# AlienWhoopF7-ESP32.net
KiCad netlist of a schematic drawn in EAGLE
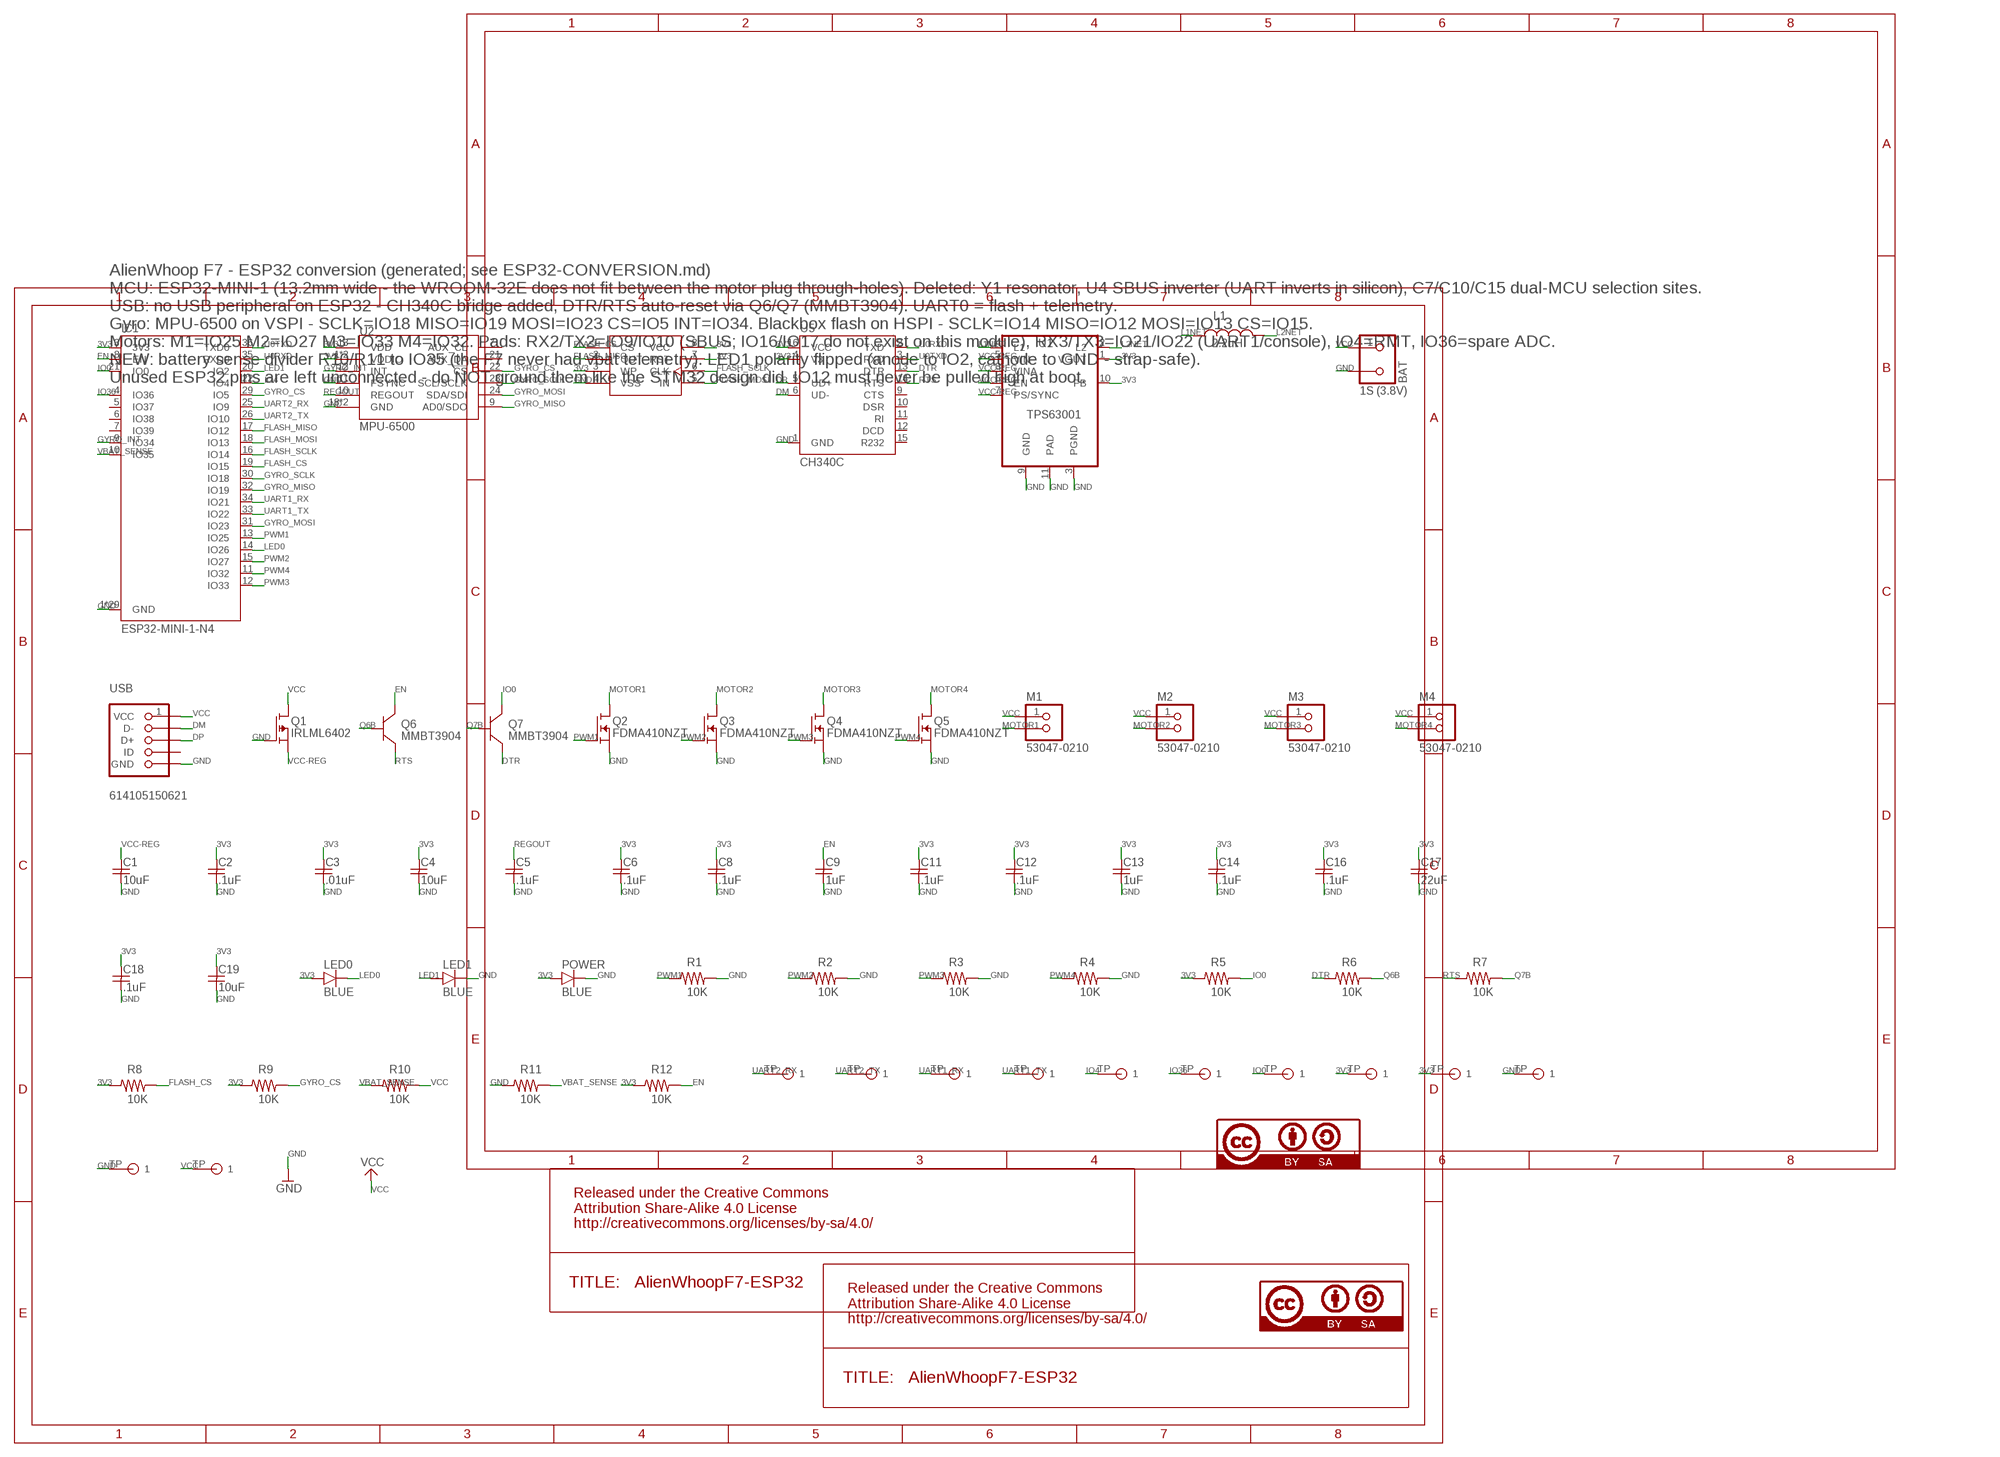
[diagram p0: schematic, sheet 1]

(export (version "E")
  (design (tool "Eeschema 10.0.6"))
  (components
    (comp (ref "3.3V")
      (value "TESTPAD")
      (footprint "eagle-import:TESTPAD")
      (libsource (lib "eagle-import") (part "TESTPAD"))
    )
    (comp (ref "3V3")
      (value "TESTPAD")
      (footprint "eagle-import:TESTPAD")
      (libsource (lib "eagle-import") (part "TESTPAD"))
    )
    (comp (ref "BAT")
      (value "1S (3.8V)")
      (footprint "eagle-import:S2B-PH-K-S")
      (fields (field (name "MF") "JST") (field (name "MPN") "S2B-PH-K-S"))
      (libsource (lib "eagle-import") (part "JST-PH-BAT"))
    )
    (comp (ref "BOOT")
      (value "TESTPAD")
      (footprint "eagle-import:TESTPAD")
      (libsource (lib "eagle-import") (part "TESTPAD"))
    )
    (comp (ref "C1")
      (value "10uF")
      (footprint "eagle-import:YUDEN-CAP-0805")
      (fields (field (name "MF") "Taiyo Yuden") (field (name "MPN") "JMK212AB7106KG-T"))
      (libsource (lib "eagle-import") (part "CAPACITOR10UF"))
    )
    (comp (ref "C2")
      (value ".1uF")
      (footprint "eagle-import:MUR-CAP-0603")
      (fields (field (name "MF") "Murata") (field (name "MPN") "GRM188R71C104KA01D"))
      (libsource (lib "eagle-import") (part "CAPACITOR.1UF"))
    )
    (comp (ref "C3")
      (value ".01uF")
      (footprint "eagle-import:MUR-CAP-0603")
      (fields (field (name "MF") "Murata") (field (name "MPN") "GRM188R71C103KA01D"))
      (libsource (lib "eagle-import") (part "CAPACITOR.01UF"))
    )
    (comp (ref "C4")
      (value "10uF")
      (footprint "eagle-import:YUDEN-CAP-0805")
      (fields (field (name "MF") "Taiyo Yuden") (field (name "MPN") "JMK212AB7106KG-T"))
      (libsource (lib "eagle-import") (part "CAPACITOR10UF"))
    )
    (comp (ref "C5")
      (value ".1uF")
      (footprint "eagle-import:MUR-CAP-0603")
      (fields (field (name "MF") "Murata") (field (name "MPN") "GRM188R71C104KA01D"))
      (libsource (lib "eagle-import") (part "CAPACITOR.1UF"))
    )
    (comp (ref "C6")
      (value ".1uF")
      (footprint "eagle-import:MUR-CAP-0603")
      (fields (field (name "MF") "Murata") (field (name "MPN") "GRM188R71C104KA01D"))
      (libsource (lib "eagle-import") (part "CAPACITOR.1UF"))
    )
    (comp (ref "C8")
      (value ".1uF")
      (footprint "eagle-import:MUR-CAP-0603")
      (fields (field (name "MF") "Murata") (field (name "MPN") "GRM188R71C104KA01D"))
      (libsource (lib "eagle-import") (part "CAPACITOR.1UF"))
    )
    (comp (ref "C9")
      (value "1uF")
      (footprint "eagle-import:MUR-CAP-0603")
      (fields (field (name "MF") "Murata") (field (name "MPN") "GRM188R71C105KA12D"))
      (libsource (lib "eagle-import") (part "CAPACITOR1UF"))
    )
    (comp (ref "C11")
      (value ".1uF")
      (footprint "eagle-import:MUR-CAP-0603")
      (fields (field (name "MF") "Murata") (field (name "MPN") "GRM188R71C104KA01D"))
      (libsource (lib "eagle-import") (part "CAPACITOR.1UF"))
    )
    (comp (ref "C12")
      (value ".1uF")
      (footprint "eagle-import:MUR-CAP-0603")
      (fields (field (name "MF") "Murata") (field (name "MPN") "GRM188R71C104KA01D"))
      (libsource (lib "eagle-import") (part "CAPACITOR.1UF"))
    )
    (comp (ref "C13")
      (value "1uF")
      (footprint "eagle-import:MUR-CAP-0603")
      (fields (field (name "MF") "Murata") (field (name "MPN") "GRM188R71C105KA12D"))
      (libsource (lib "eagle-import") (part "CAPACITOR1UF"))
    )
    (comp (ref "C14")
      (value ".1uF")
      (footprint "eagle-import:MUR-CAP-0603")
      (fields (field (name "MF") "Murata") (field (name "MPN") "GRM188R71C104KA01D"))
      (libsource (lib "eagle-import") (part "CAPACITOR.1UF"))
    )
    (comp (ref "C16")
      (value ".1uF")
      (footprint "eagle-import:MUR-CAP-0603")
      (fields (field (name "MF") "Murata") (field (name "MPN") "GRM188R71C104KA01D"))
      (libsource (lib "eagle-import") (part "CAPACITOR.1UF"))
    )
    (comp (ref "C17")
      (value "22uF")
      (footprint "eagle-import:YUDEN-CAP-0805")
      (fields (field (name "MF") "Taiyo Yuden") (field (name "MPN") "JMK212BJ226MG-T"))
      (libsource (lib "eagle-import") (part "CAPACITOR22UF"))
    )
    (comp (ref "C18")
      (value ".1uF")
      (footprint "eagle-import:MUR-CAP-0603")
      (fields (field (name "MF") "Murata") (field (name "MPN") "GRM188R71C104KA01D"))
      (libsource (lib "eagle-import") (part "CAPACITOR.1UF"))
    )
    (comp (ref "C19")
      (value "10uF")
      (footprint "eagle-import:YUDEN-CAP-0805")
      (fields (field (name "MF") "Taiyo Yuden") (field (name "MPN") "JMK212AB7106KG-T"))
      (libsource (lib "eagle-import") (part "CAPACITOR10UF"))
    )
    (comp (ref "GND")
      (value "TESTPAD")
      (footprint "eagle-import:TESTPAD")
      (libsource (lib "eagle-import") (part "TESTPAD"))
    )
    (comp (ref "GND@1")
      (value "TESTPAD")
      (footprint "eagle-import:TESTPAD")
      (libsource (lib "eagle-import") (part "TESTPAD"))
    )
    (comp (ref "IC1")
      (value "ESP32-MINI-1-N4")
      (footprint "eagle-import:ESP32-MINI-1")
      (libsource (lib "eagle-import") (part "ESP32-MINI-1"))
    )
    (comp (ref "IO4")
      (value "TESTPAD")
      (footprint "eagle-import:TESTPAD")
      (libsource (lib "eagle-import") (part "TESTPAD"))
    )
    (comp (ref "IO36")
      (value "TESTPAD")
      (footprint "eagle-import:TESTPAD")
      (libsource (lib "eagle-import") (part "TESTPAD"))
    )
    (comp (ref "L1")
      (value "2.2uH")
      (footprint "eagle-import:DFE201612E-2R2M-P2")
      (libsource (lib "eagle-import") (part "DFE201612E-2R2M-P2"))
    )
    (comp (ref "LED0")
      (value "BLUE")
      (footprint "eagle-import:SMD-CHIP-LED-0805")
      (fields (field (name "MF") "Kingbright") (field (name "MPN") "APHCM2012QBC/D-F01"))
      (libsource (lib "eagle-import") (part "SMD-CHIP-LED-0805"))
    )
    (comp (ref "LED1")
      (value "BLUE")
      (footprint "eagle-import:SMD-CHIP-LED-0805")
      (fields (field (name "MF") "Kingbright") (field (name "MPN") "APHCM2012QBC/D-F01"))
      (libsource (lib "eagle-import") (part "SMD-CHIP-LED-0805"))
    )
    (comp (ref "M1")
      (value "53047-0210")
      (footprint "eagle-import:PICO-53047-02")
      (fields (field (name "MF") "MOLEX"))
      (libsource (lib "eagle-import") (part "PICO-1.25-MOTOR"))
    )
    (comp (ref "M2")
      (value "53047-0210")
      (footprint "eagle-import:PICO-53047-02")
      (fields (field (name "MF") "MOLEX"))
      (libsource (lib "eagle-import") (part "PICO-1.25-MOTOR"))
    )
    (comp (ref "M3")
      (value "53047-0210")
      (footprint "eagle-import:PICO-53047-02")
      (fields (field (name "MF") "MOLEX"))
      (libsource (lib "eagle-import") (part "PICO-1.25-MOTOR"))
    )
    (comp (ref "M4")
      (value "53047-0210")
      (footprint "eagle-import:PICO-53047-02")
      (fields (field (name "MF") "MOLEX"))
      (libsource (lib "eagle-import") (part "PICO-1.25-MOTOR"))
    )
    (comp (ref "POWER")
      (value "BLUE")
      (footprint "eagle-import:SMD-CHIP-LED-0805")
      (fields (field (name "MF") "Kingbright") (field (name "MPN") "APHCM2012QBC/D-F01"))
      (libsource (lib "eagle-import") (part "SMD-CHIP-LED-0805"))
    )
    (comp (ref "Q1")
      (value "IRLML6402")
      (footprint "eagle-import:SOT-23")
      (fields (field (name "MF") "IR"))
      (libsource (lib "eagle-import") (part "MOSFET-P"))
    )
    (comp (ref "Q2")
      (value "FDMA410NZT")
      (footprint "eagle-import:MICROFET-2X2")
      (fields (field (name "MF") "Fairchild") (field (name "MPN") "FDMA410NZ"))
      (libsource (lib "eagle-import") (part "FDMA410NZ"))
    )
    (comp (ref "Q3")
      (value "FDMA410NZT")
      (footprint "eagle-import:MICROFET-2X2")
      (fields (field (name "MF") "Fairchild") (field (name "MPN") "FDMA410NZ"))
      (libsource (lib "eagle-import") (part "FDMA410NZ"))
    )
    (comp (ref "Q4")
      (value "FDMA410NZT")
      (footprint "eagle-import:MICROFET-2X2")
      (fields (field (name "MF") "Fairchild") (field (name "MPN") "FDMA410NZ"))
      (libsource (lib "eagle-import") (part "FDMA410NZ"))
    )
    (comp (ref "Q5")
      (value "FDMA410NZT")
      (footprint "eagle-import:MICROFET-2X2")
      (fields (field (name "MF") "Fairchild") (field (name "MPN") "FDMA410NZ"))
      (libsource (lib "eagle-import") (part "FDMA410NZ"))
    )
    (comp (ref "Q6")
      (value "MMBT3904")
      (footprint "eagle-import:SOT23")
      (libsource (lib "eagle-import") (part "MMBT3904"))
    )
    (comp (ref "Q7")
      (value "MMBT3904")
      (footprint "eagle-import:SOT23")
      (libsource (lib "eagle-import") (part "MMBT3904"))
    )
    (comp (ref "R1")
      (value "10K")
      (footprint "eagle-import:VISH-RES-0603")
      (fields (field (name "MF") "Vishay") (field (name "MPN") "CRCW060310K0FKEAHP"))
      (libsource (lib "eagle-import") (part "RESISTOR10K"))
    )
    (comp (ref "R2")
      (value "10K")
      (footprint "eagle-import:VISH-RES-0603")
      (fields (field (name "MF") "Vishay") (field (name "MPN") "CRCW060310K0FKEAHP"))
      (libsource (lib "eagle-import") (part "RESISTOR10K"))
    )
    (comp (ref "R3")
      (value "10K")
      (footprint "eagle-import:VISH-RES-0603")
      (fields (field (name "MF") "Vishay") (field (name "MPN") "CRCW060310K0FKEAHP"))
      (libsource (lib "eagle-import") (part "RESISTOR10K"))
    )
    (comp (ref "R4")
      (value "10K")
      (footprint "eagle-import:VISH-RES-0603")
      (fields (field (name "MF") "Vishay") (field (name "MPN") "CRCW060310K0FKEAHP"))
      (libsource (lib "eagle-import") (part "RESISTOR10K"))
    )
    (comp (ref "R5")
      (value "10K")
      (footprint "eagle-import:VISH-RES-0603")
      (fields (field (name "MF") "Vishay") (field (name "MPN") "CRCW060310K0FKEAHP"))
      (libsource (lib "eagle-import") (part "RESISTOR10K"))
    )
    (comp (ref "R6")
      (value "10K")
      (footprint "eagle-import:VISH-RES-0603")
      (fields (field (name "MF") "Vishay") (field (name "MPN") "CRCW060310K0FKEAHP"))
      (libsource (lib "eagle-import") (part "RESISTOR10K"))
    )
    (comp (ref "R7")
      (value "10K")
      (footprint "eagle-import:VISH-RES-0603")
      (fields (field (name "MF") "Vishay") (field (name "MPN") "CRCW060310K0FKEAHP"))
      (libsource (lib "eagle-import") (part "RESISTOR10K"))
    )
    (comp (ref "R8")
      (value "10K")
      (footprint "eagle-import:VISH-RES-0603")
      (fields (field (name "MF") "Vishay") (field (name "MPN") "CRCW060310K0FKEAHP"))
      (libsource (lib "eagle-import") (part "RESISTOR10K"))
    )
    (comp (ref "R9")
      (value "10K")
      (footprint "eagle-import:VISH-RES-0603")
      (fields (field (name "MF") "Vishay") (field (name "MPN") "CRCW060310K0FKEAHP"))
      (libsource (lib "eagle-import") (part "RESISTOR10K"))
    )
    (comp (ref "R10")
      (value "10K")
      (footprint "eagle-import:VISH-RES-0603")
      (fields (field (name "MF") "Vishay") (field (name "MPN") "CRCW060310K0FKEAHP"))
      (libsource (lib "eagle-import") (part "RESISTOR10K"))
    )
    (comp (ref "R11")
      (value "10K")
      (footprint "eagle-import:VISH-RES-0603")
      (fields (field (name "MF") "Vishay") (field (name "MPN") "CRCW060310K0FKEAHP"))
      (libsource (lib "eagle-import") (part "RESISTOR10K"))
    )
    (comp (ref "R12")
      (value "10K")
      (footprint "eagle-import:VISH-RES-0603")
      (fields (field (name "MF") "Vishay") (field (name "MPN") "CRCW060310K0FKEAHP"))
      (libsource (lib "eagle-import") (part "RESISTOR10K"))
    )
    (comp (ref "RX2")
      (value "TESTPAD")
      (footprint "eagle-import:TESTPAD")
      (libsource (lib "eagle-import") (part "TESTPAD"))
    )
    (comp (ref "RX3")
      (value "TESTPAD")
      (footprint "eagle-import:TESTPAD")
      (libsource (lib "eagle-import") (part "TESTPAD"))
    )
    (comp (ref "TX2")
      (value "TESTPAD")
      (footprint "eagle-import:TESTPAD")
      (libsource (lib "eagle-import") (part "TESTPAD"))
    )
    (comp (ref "TX3")
      (value "TESTPAD")
      (footprint "eagle-import:TESTPAD")
      (libsource (lib "eagle-import") (part "TESTPAD"))
    )
    (comp (ref "U1")
      (value "TPS63001")
      (footprint "eagle-import:VSON-N10")
      (fields (field (name "MF") "TI") (field (name "MPN") "TPS63001DRCR"))
      (libsource (lib "eagle-import") (part "TPS630XX-TPS63001"))
    )
    (comp (ref "U2")
      (value "MPU-6500")
      (footprint "eagle-import:QFN24_PAD")
      (libsource (lib "eagle-import") (part "MPU-9250"))
    )
    (comp (ref "U3")
      (value "MX25L6406EM2I-12G")
      (footprint "eagle-import:M25P32")
      (libsource (lib "eagle-import") (part "M25P32"))
    )
    (comp (ref "U5")
      (value "CH340C")
      (footprint "eagle-import:SOP16")
      (libsource (lib "eagle-import") (part "CH340C"))
    )
    (comp (ref "USB")
      (value "614105150621")
      (footprint "eagle-import:USB-BFPV")
      (libsource (lib "eagle-import") (part "MICROUSBUSB-BFPV"))
    )
    (comp (ref "VCC@1")
      (value "TESTPAD")
      (footprint "eagle-import:TESTPAD")
      (libsource (lib "eagle-import") (part "TESTPAD"))
    )
  )
  (nets
    (net (code "1") (name "/3V3") (class "Default")
      (node (ref "3.3V") (pin "TP") (pinfunction "1_TP") (pintype "bidirectional"))
      (node (ref "3V3") (pin "TP") (pinfunction "1_TP") (pintype "bidirectional"))
      (node (ref "C11") (pin "1") (pinfunction "1_1") (pintype "passive"))
      (node (ref "C12") (pin "1") (pinfunction "1_1") (pintype "passive"))
      (node (ref "C13") (pin "1") (pinfunction "1_1") (pintype "passive"))
      (node (ref "C14") (pin "1") (pinfunction "1_1") (pintype "passive"))
      (node (ref "C16") (pin "1") (pinfunction "1_1") (pintype "passive"))
      (node (ref "C17") (pin "1") (pinfunction "1_1") (pintype "passive"))
      (node (ref "C18") (pin "1") (pinfunction "1_1") (pintype "passive"))
      (node (ref "C19") (pin "1") (pinfunction "1_1") (pintype "passive"))
      (node (ref "C2") (pin "1") (pinfunction "1_1") (pintype "passive"))
      (node (ref "C3") (pin "1") (pinfunction "1_1") (pintype "passive"))
      (node (ref "C4") (pin "1") (pinfunction "1_1") (pintype "passive"))
      (node (ref "C6") (pin "1") (pinfunction "1_1") (pintype "passive"))
      (node (ref "C8") (pin "1") (pinfunction "1_1") (pintype "passive"))
      (node (ref "IC1") (pin "3") (pinfunction "3V3_3") (pintype "bidirectional"))
      (node (ref "LED0") (pin "A") (pinfunction "A_A") (pintype "passive"))
      (node (ref "POWER") (pin "A") (pinfunction "A_A") (pintype "passive"))
      (node (ref "R12") (pin "2") (pinfunction "2_2") (pintype "passive"))
      (node (ref "R5") (pin "2") (pinfunction "2_2") (pintype "passive"))
      (node (ref "R8") (pin "2") (pinfunction "2_2") (pintype "passive"))
      (node (ref "R9") (pin "2") (pinfunction "2_2") (pintype "passive"))
      (node (ref "U1") (pin "1") (pinfunction "VOUT_1") (pintype "bidirectional"))
      (node (ref "U1") (pin "10") (pinfunction "FB_10") (pintype "bidirectional"))
      (node (ref "U2") (pin "1") (pinfunction "VDDIO_1") (pintype "bidirectional"))
      (node (ref "U2") (pin "13") (pinfunction "VDD_13") (pintype "bidirectional"))
      (node (ref "U2") (pin "8") (pinfunction "VDDIO_8") (pintype "bidirectional"))
      (node (ref "U3") (pin "3") (pinfunction "WP_3") (pintype "bidirectional"))
      (node (ref "U3") (pin "7") (pinfunction "RST_7") (pintype "bidirectional"))
      (node (ref "U3") (pin "8") (pinfunction "VCC_8") (pintype "power_in"))
      (node (ref "U5") (pin "16") (pinfunction "VCC_16") (pintype "bidirectional"))
      (node (ref "U5") (pin "4") (pinfunction "V3_4") (pintype "bidirectional"))
    )
    (net (code "2") (name "/DM") (class "Default")
      (node (ref "U5") (pin "6") (pinfunction "UD-_6") (pintype "bidirectional"))
      (node (ref "USB") (pin "2") (pinfunction "D-_2") (pintype "passive"))
    )
    (net (code "3") (name "/DP") (class "Default")
      (node (ref "U5") (pin "5") (pinfunction "UD+_5") (pintype "bidirectional"))
      (node (ref "USB") (pin "3") (pinfunction "D+_3") (pintype "passive"))
    )
    (net (code "4") (name "/DTR") (class "Default")
      (node (ref "Q7") (pin "2") (pinfunction "E_2") (pintype "bidirectional"))
      (node (ref "R6") (pin "2") (pinfunction "2_2") (pintype "passive"))
      (node (ref "U5") (pin "13") (pinfunction "DTR_13") (pintype "bidirectional"))
    )
    (net (code "5") (name "/EN") (class "Default")
      (node (ref "C9") (pin "1") (pinfunction "1_1") (pintype "passive"))
      (node (ref "IC1") (pin "8") (pinfunction "EN_8") (pintype "bidirectional"))
      (node (ref "Q6") (pin "3") (pinfunction "C_3") (pintype "bidirectional"))
      (node (ref "R12") (pin "1") (pinfunction "1_1") (pintype "passive"))
    )
    (net (code "6") (name "/FLASH_CS") (class "Default")
      (node (ref "IC1") (pin "19") (pinfunction "IO15_19") (pintype "bidirectional"))
      (node (ref "R8") (pin "1") (pinfunction "1_1") (pintype "passive"))
      (node (ref "U3") (pin "1") (pinfunction "CS_1") (pintype "bidirectional"))
    )
    (net (code "7") (name "/FLASH_MISO") (class "Default")
      (node (ref "IC1") (pin "17") (pinfunction "IO12_17") (pintype "bidirectional"))
      (node (ref "U3") (pin "2") (pinfunction "OUT_2") (pintype "output"))
    )
    (net (code "8") (name "/FLASH_MOSI") (class "Default")
      (node (ref "IC1") (pin "18") (pinfunction "IO13_18") (pintype "bidirectional"))
      (node (ref "U3") (pin "5") (pinfunction "IN_5") (pintype "input"))
    )
    (net (code "9") (name "/FLASH_SCLK") (class "Default")
      (node (ref "IC1") (pin "16") (pinfunction "IO14_16") (pintype "bidirectional"))
      (node (ref "U3") (pin "6") (pinfunction "CLK_6") (pintype "bidirectional"))
    )
    (net (code "10") (name "/GYRO_CS") (class "Default")
      (node (ref "IC1") (pin "29") (pinfunction "IO5_29") (pintype "bidirectional"))
      (node (ref "R9") (pin "1") (pinfunction "1_1") (pintype "passive"))
      (node (ref "U2") (pin "22") (pinfunction "~{CS}_22") (pintype "bidirectional"))
    )
    (net (code "11") (name "/GYRO_INT") (class "Default")
      (node (ref "IC1") (pin "9") (pinfunction "IO34_9") (pintype "bidirectional"))
      (node (ref "U2") (pin "12") (pinfunction "INT_12") (pintype "bidirectional"))
    )
    (net (code "12") (name "/GYRO_MISO") (class "Default")
      (node (ref "IC1") (pin "32") (pinfunction "IO19_32") (pintype "bidirectional"))
      (node (ref "U2") (pin "9") (pinfunction "AD0/SDO_9") (pintype "bidirectional"))
    )
    (net (code "13") (name "/GYRO_MOSI") (class "Default")
      (node (ref "IC1") (pin "31") (pinfunction "IO23_31") (pintype "bidirectional"))
      (node (ref "U2") (pin "24") (pinfunction "SDA/SDI_24") (pintype "bidirectional"))
    )
    (net (code "14") (name "/GYRO_SCLK") (class "Default")
      (node (ref "IC1") (pin "30") (pinfunction "IO18_30") (pintype "bidirectional"))
      (node (ref "U2") (pin "23") (pinfunction "SCL/SCLK_23") (pintype "bidirectional"))
    )
    (net (code "15") (name "/IO0") (class "Default")
      (node (ref "BOOT") (pin "TP") (pinfunction "1_TP") (pintype "bidirectional"))
      (node (ref "IC1") (pin "21") (pinfunction "IO0_21") (pintype "bidirectional"))
      (node (ref "Q7") (pin "3") (pinfunction "C_3") (pintype "bidirectional"))
      (node (ref "R5") (pin "1") (pinfunction "1_1") (pintype "passive"))
    )
    (net (code "16") (name "/IO4") (class "Default")
      (node (ref "IC1") (pin "22") (pinfunction "IO4_22") (pintype "bidirectional"))
      (node (ref "IO4") (pin "TP") (pinfunction "1_TP") (pintype "bidirectional"))
    )
    (net (code "17") (name "/IO36") (class "Default")
      (node (ref "IC1") (pin "4") (pinfunction "IO36_4") (pintype "bidirectional"))
      (node (ref "IO36") (pin "TP") (pinfunction "1_TP") (pintype "bidirectional"))
    )
    (net (code "18") (name "/L1NET") (class "Default")
      (node (ref "L1") (pin "P$1") (pinfunction "1_P$1") (pintype "passive"))
      (node (ref "U1") (pin "4") (pinfunction "L1_4") (pintype "bidirectional"))
    )
    (net (code "19") (name "/L2NET") (class "Default")
      (node (ref "L1") (pin "P$2") (pinfunction "2_P$2") (pintype "passive"))
      (node (ref "U1") (pin "2") (pinfunction "L2_2") (pintype "bidirectional"))
    )
    (net (code "20") (name "/LED0") (class "Default")
      (node (ref "IC1") (pin "14") (pinfunction "IO26_14") (pintype "bidirectional"))
      (node (ref "LED0") (pin "C") (pinfunction "C_C") (pintype "passive"))
    )
    (net (code "21") (name "/LED1") (class "Default")
      (node (ref "IC1") (pin "20") (pinfunction "IO2_20") (pintype "bidirectional"))
      (node (ref "LED1") (pin "A") (pinfunction "A_A") (pintype "passive"))
    )
    (net (code "22") (name "/MOTOR1") (class "Default")
      (node (ref "M1") (pin "2") (pinfunction "2_2") (pintype "passive"))
      (node (ref "Q2") (pin "D") (pinfunction "D_D") (pintype "bidirectional"))
      (node (ref "Q2") (pin "D1") (pinfunction "D_D1") (pintype "bidirectional"))
      (node (ref "Q2") (pin "D2") (pinfunction "D_D2") (pintype "bidirectional"))
      (node (ref "Q2") (pin "D3") (pinfunction "D_D3") (pintype "bidirectional"))
      (node (ref "Q2") (pin "D4") (pinfunction "D_D4") (pintype "bidirectional"))
    )
    (net (code "23") (name "/MOTOR2") (class "Default")
      (node (ref "M2") (pin "2") (pinfunction "2_2") (pintype "passive"))
      (node (ref "Q3") (pin "D") (pinfunction "D_D") (pintype "bidirectional"))
      (node (ref "Q3") (pin "D1") (pinfunction "D_D1") (pintype "bidirectional"))
      (node (ref "Q3") (pin "D2") (pinfunction "D_D2") (pintype "bidirectional"))
      (node (ref "Q3") (pin "D3") (pinfunction "D_D3") (pintype "bidirectional"))
      (node (ref "Q3") (pin "D4") (pinfunction "D_D4") (pintype "bidirectional"))
    )
    (net (code "24") (name "/MOTOR3") (class "Default")
      (node (ref "M3") (pin "2") (pinfunction "2_2") (pintype "passive"))
      (node (ref "Q4") (pin "D") (pinfunction "D_D") (pintype "bidirectional"))
      (node (ref "Q4") (pin "D1") (pinfunction "D_D1") (pintype "bidirectional"))
      (node (ref "Q4") (pin "D2") (pinfunction "D_D2") (pintype "bidirectional"))
      (node (ref "Q4") (pin "D3") (pinfunction "D_D3") (pintype "bidirectional"))
      (node (ref "Q4") (pin "D4") (pinfunction "D_D4") (pintype "bidirectional"))
    )
    (net (code "25") (name "/MOTOR4") (class "Default")
      (node (ref "M4") (pin "2") (pinfunction "2_2") (pintype "passive"))
      (node (ref "Q5") (pin "D") (pinfunction "D_D") (pintype "bidirectional"))
      (node (ref "Q5") (pin "D1") (pinfunction "D_D1") (pintype "bidirectional"))
      (node (ref "Q5") (pin "D2") (pinfunction "D_D2") (pintype "bidirectional"))
      (node (ref "Q5") (pin "D3") (pinfunction "D_D3") (pintype "bidirectional"))
      (node (ref "Q5") (pin "D4") (pinfunction "D_D4") (pintype "bidirectional"))
    )
    (net (code "26") (name "/PWM1") (class "Default")
      (node (ref "IC1") (pin "13") (pinfunction "IO25_13") (pintype "bidirectional"))
      (node (ref "Q2") (pin "G") (pinfunction "G_G") (pintype "bidirectional"))
      (node (ref "R1") (pin "2") (pinfunction "2_2") (pintype "passive"))
    )
    (net (code "27") (name "/PWM2") (class "Default")
      (node (ref "IC1") (pin "15") (pinfunction "IO27_15") (pintype "bidirectional"))
      (node (ref "Q3") (pin "G") (pinfunction "G_G") (pintype "bidirectional"))
      (node (ref "R2") (pin "2") (pinfunction "2_2") (pintype "passive"))
    )
    (net (code "28") (name "/PWM3") (class "Default")
      (node (ref "IC1") (pin "12") (pinfunction "IO33_12") (pintype "bidirectional"))
      (node (ref "Q4") (pin "G") (pinfunction "G_G") (pintype "bidirectional"))
      (node (ref "R3") (pin "2") (pinfunction "2_2") (pintype "passive"))
    )
    (net (code "29") (name "/PWM4") (class "Default")
      (node (ref "IC1") (pin "11") (pinfunction "IO32_11") (pintype "bidirectional"))
      (node (ref "Q5") (pin "G") (pinfunction "G_G") (pintype "bidirectional"))
      (node (ref "R4") (pin "2") (pinfunction "2_2") (pintype "passive"))
    )
    (net (code "30") (name "/Q6B") (class "Default")
      (node (ref "Q6") (pin "1") (pinfunction "B_1") (pintype "bidirectional"))
      (node (ref "R6") (pin "1") (pinfunction "1_1") (pintype "passive"))
    )
    (net (code "31") (name "/Q7B") (class "Default")
      (node (ref "Q7") (pin "1") (pinfunction "B_1") (pintype "bidirectional"))
      (node (ref "R7") (pin "1") (pinfunction "1_1") (pintype "passive"))
    )
    (net (code "32") (name "/REGOUT") (class "Default")
      (node (ref "C5") (pin "1") (pinfunction "1_1") (pintype "passive"))
      (node (ref "U2") (pin "10") (pinfunction "REGOUT_10") (pintype "bidirectional"))
    )
    (net (code "33") (name "/RTS") (class "Default")
      (node (ref "Q6") (pin "2") (pinfunction "E_2") (pintype "bidirectional"))
      (node (ref "R7") (pin "2") (pinfunction "2_2") (pintype "passive"))
      (node (ref "U5") (pin "14") (pinfunction "RTS_14") (pintype "bidirectional"))
    )
    (net (code "34") (name "/U0RXD") (class "Default")
      (node (ref "IC1") (pin "35") (pinfunction "RXD0_35") (pintype "bidirectional"))
      (node (ref "U5") (pin "2") (pinfunction "TXD_2") (pintype "bidirectional"))
    )
    (net (code "35") (name "/U0TXD") (class "Default")
      (node (ref "IC1") (pin "36") (pinfunction "TXD0_36") (pintype "bidirectional"))
      (node (ref "U5") (pin "3") (pinfunction "RXD_3") (pintype "bidirectional"))
    )
    (net (code "36") (name "/UART1_RX") (class "Default")
      (node (ref "IC1") (pin "34") (pinfunction "IO21_34") (pintype "bidirectional"))
      (node (ref "RX3") (pin "TP") (pinfunction "1_TP") (pintype "bidirectional"))
    )
    (net (code "37") (name "/UART1_TX") (class "Default")
      (node (ref "IC1") (pin "33") (pinfunction "IO22_33") (pintype "bidirectional"))
      (node (ref "TX3") (pin "TP") (pinfunction "1_TP") (pintype "bidirectional"))
    )
    (net (code "38") (name "/UART2_RX") (class "Default")
      (node (ref "IC1") (pin "25") (pinfunction "IO9_25") (pintype "bidirectional"))
      (node (ref "RX2") (pin "TP") (pinfunction "1_TP") (pintype "bidirectional"))
    )
    (net (code "39") (name "/UART2_TX") (class "Default")
      (node (ref "IC1") (pin "26") (pinfunction "IO10_26") (pintype "bidirectional"))
      (node (ref "TX2") (pin "TP") (pinfunction "1_TP") (pintype "bidirectional"))
    )
    (net (code "40") (name "/VBAT_SENSE") (class "Default")
      (node (ref "IC1") (pin "10") (pinfunction "IO35_10") (pintype "bidirectional"))
      (node (ref "R10") (pin "2") (pinfunction "2_2") (pintype "passive"))
      (node (ref "R11") (pin "1") (pinfunction "1_1") (pintype "passive"))
    )
    (net (code "41") (name "/VCC-REG") (class "Default")
      (node (ref "C1") (pin "1") (pinfunction "1_1") (pintype "passive"))
      (node (ref "Q1") (pin "2") (pinfunction "S_2") (pintype "bidirectional"))
      (node (ref "U1") (pin "5") (pinfunction "VIN_5") (pintype "bidirectional"))
      (node (ref "U1") (pin "6") (pinfunction "EN_6") (pintype "bidirectional"))
      (node (ref "U1") (pin "7") (pinfunction "PS/SYNC_7") (pintype "bidirectional"))
      (node (ref "U1") (pin "8") (pinfunction "VINA_8") (pintype "bidirectional"))
    )
    (net (code "42") (name "GND") (class "Default")
      (node (ref "BAT") (pin "2") (pinfunction "2_2") (pintype "bidirectional"))
      (node (ref "C1") (pin "2") (pinfunction "2_2") (pintype "passive"))
      (node (ref "C11") (pin "2") (pinfunction "2_2") (pintype "passive"))
      (node (ref "C12") (pin "2") (pinfunction "2_2") (pintype "passive"))
      (node (ref "C13") (pin "2") (pinfunction "2_2") (pintype "passive"))
      (node (ref "C14") (pin "2") (pinfunction "2_2") (pintype "passive"))
      (node (ref "C16") (pin "2") (pinfunction "2_2") (pintype "passive"))
      (node (ref "C17") (pin "2") (pinfunction "2_2") (pintype "passive"))
      (node (ref "C18") (pin "2") (pinfunction "2_2") (pintype "passive"))
      (node (ref "C19") (pin "2") (pinfunction "2_2") (pintype "passive"))
      (node (ref "C2") (pin "2") (pinfunction "2_2") (pintype "passive"))
      (node (ref "C3") (pin "2") (pinfunction "2_2") (pintype "passive"))
      (node (ref "C4") (pin "2") (pinfunction "2_2") (pintype "passive"))
      (node (ref "C5") (pin "2") (pinfunction "2_2") (pintype "passive"))
      (node (ref "C6") (pin "2") (pinfunction "2_2") (pintype "passive"))
      (node (ref "C8") (pin "2") (pinfunction "2_2") (pintype "passive"))
      (node (ref "C9") (pin "2") (pinfunction "2_2") (pintype "passive"))
      (node (ref "GND") (pin "TP") (pinfunction "1_TP") (pintype "bidirectional"))
      (node (ref "GND@1") (pin "TP") (pinfunction "1_TP") (pintype "bidirectional"))
      (node (ref "IC1") (pin "1") (pinfunction "GND_1") (pintype "bidirectional"))
      (node (ref "IC1") (pin "2") (pinfunction "GND_2") (pintype "bidirectional"))
      (node (ref "IC1") (pin "27") (pinfunction "GND_27") (pintype "bidirectional"))
      (node (ref "IC1") (pin "38") (pinfunction "GND_38") (pintype "bidirectional"))
      (node (ref "IC1") (pin "39") (pinfunction "GND_39") (pintype "bidirectional"))
      (node (ref "IC1") (pin "40") (pinfunction "GND_40") (pintype "bidirectional"))
      (node (ref "IC1") (pin "41") (pinfunction "GND_41") (pintype "bidirectional"))
      (node (ref "IC1") (pin "42") (pinfunction "GND_42") (pintype "bidirectional"))
      (node (ref "IC1") (pin "43") (pinfunction "GND_43") (pintype "bidirectional"))
      (node (ref "IC1") (pin "44") (pinfunction "GND_44") (pintype "bidirectional"))
      (node (ref "IC1") (pin "45") (pinfunction "GND_45") (pintype "bidirectional"))
      (node (ref "IC1") (pin "46") (pinfunction "GND_46") (pintype "bidirectional"))
      (node (ref "IC1") (pin "47") (pinfunction "GND_47") (pintype "bidirectional"))
      (node (ref "IC1") (pin "48") (pinfunction "GND_48") (pintype "bidirectional"))
      (node (ref "IC1") (pin "49") (pinfunction "GND_49") (pintype "bidirectional"))
      (node (ref "IC1") (pin "50") (pinfunction "GND_50") (pintype "bidirectional"))
      (node (ref "IC1") (pin "51") (pinfunction "GND_51") (pintype "bidirectional"))
      (node (ref "IC1") (pin "52") (pinfunction "GND_52") (pintype "bidirectional"))
      (node (ref "IC1") (pin "53") (pinfunction "GND_53") (pintype "bidirectional"))
      (node (ref "IC1") (pin "54") (pinfunction "GND_54") (pintype "bidirectional"))
      (node (ref "IC1") (pin "55") (pinfunction "GND_55") (pintype "bidirectional"))
      (node (ref "IC1") (pin "T1") (pinfunction "GND_T1") (pintype "bidirectional"))
      (node (ref "IC1") (pin "T2") (pinfunction "GND_T2") (pintype "bidirectional"))
      (node (ref "IC1") (pin "T3") (pinfunction "GND_T3") (pintype "bidirectional"))
      (node (ref "IC1") (pin "T4") (pinfunction "GND_T4") (pintype "bidirectional"))
      (node (ref "IC1") (pin "T5") (pinfunction "GND_T5") (pintype "bidirectional"))
      (node (ref "IC1") (pin "T6") (pinfunction "GND_T6") (pintype "bidirectional"))
      (node (ref "IC1") (pin "T7") (pinfunction "GND_T7") (pintype "bidirectional"))
      (node (ref "IC1") (pin "T8") (pinfunction "GND_T8") (pintype "bidirectional"))
      (node (ref "LED1") (pin "C") (pinfunction "C_C") (pintype "passive"))
      (node (ref "POWER") (pin "C") (pinfunction "C_C") (pintype "passive"))
      (node (ref "Q1") (pin "1") (pinfunction "G_1") (pintype "bidirectional"))
      (node (ref "Q2") (pin "S") (pinfunction "S_S") (pintype "bidirectional"))
      (node (ref "Q2") (pin "S1") (pinfunction "S_S1") (pintype "bidirectional"))
      (node (ref "Q3") (pin "S") (pinfunction "S_S") (pintype "bidirectional"))
      (node (ref "Q3") (pin "S1") (pinfunction "S_S1") (pintype "bidirectional"))
      (node (ref "Q4") (pin "S") (pinfunction "S_S") (pintype "bidirectional"))
      (node (ref "Q4") (pin "S1") (pinfunction "S_S1") (pintype "bidirectional"))
      (node (ref "Q5") (pin "S") (pinfunction "S_S") (pintype "bidirectional"))
      (node (ref "Q5") (pin "S1") (pinfunction "S_S1") (pintype "bidirectional"))
      (node (ref "R1") (pin "1") (pinfunction "1_1") (pintype "passive"))
      (node (ref "R11") (pin "2") (pinfunction "2_2") (pintype "passive"))
      (node (ref "R2") (pin "1") (pinfunction "1_1") (pintype "passive"))
      (node (ref "R3") (pin "1") (pinfunction "1_1") (pintype "passive"))
      (node (ref "R4") (pin "1") (pinfunction "1_1") (pintype "passive"))
      (node (ref "U1") (pin "11") (pinfunction "PAD_11") (pintype "bidirectional"))
      (node (ref "U1") (pin "3") (pinfunction "PGND_3") (pintype "bidirectional"))
      (node (ref "U1") (pin "9") (pinfunction "GND_9") (pintype "bidirectional"))
      (node (ref "U2") (pin "11") (pinfunction "FSYNC_11") (pintype "bidirectional"))
      (node (ref "U2") (pin "18") (pinfunction "GND_18") (pintype "bidirectional"))
      (node (ref "U2") (pin "20") (pinfunction "GND_20") (pintype "bidirectional"))
      (node (ref "U3") (pin "4") (pinfunction "VSS_4") (pintype "power_in"))
      (node (ref "U5") (pin "1") (pinfunction "GND_1") (pintype "bidirectional"))
      (node (ref "USB") (pin "5") (pinfunction "GND_5") (pintype "passive"))
      (node (ref "USB") (pin "P$6") (pinfunction "GND_P$6") (pintype "passive"))
      (node (ref "USB") (pin "P$7") (pinfunction "GND_P$7") (pintype "passive"))
    )
    (net (code "43") (name "VCC") (class "Default")
      (node (ref "BAT") (pin "1") (pinfunction "1_1") (pintype "bidirectional"))
      (node (ref "M1") (pin "1") (pinfunction "1_1") (pintype "passive"))
      (node (ref "M2") (pin "1") (pinfunction "1_1") (pintype "passive"))
      (node (ref "M3") (pin "1") (pinfunction "1_1") (pintype "passive"))
      (node (ref "M4") (pin "1") (pinfunction "1_1") (pintype "passive"))
      (node (ref "Q1") (pin "3") (pinfunction "D_3") (pintype "bidirectional"))
      (node (ref "R10") (pin "1") (pinfunction "1_1") (pintype "passive"))
      (node (ref "USB") (pin "1") (pinfunction "VCC_1") (pintype "passive"))
      (node (ref "VCC@1") (pin "TP") (pinfunction "1_TP") (pintype "bidirectional"))
    )
    (net (code "44") (name "unconnected-(IC1-IO37-Pad5)") (class "Default")
      (node (ref "IC1") (pin "5") (pinfunction "IO37_5") (pintype "bidirectional"))
    )
    (net (code "45") (name "unconnected-(IC1-IO38-Pad6)") (class "Default")
      (node (ref "IC1") (pin "6") (pinfunction "IO38_6") (pintype "bidirectional"))
    )
    (net (code "46") (name "unconnected-(IC1-IO39-Pad7)") (class "Default")
      (node (ref "IC1") (pin "7") (pinfunction "IO39_7") (pintype "bidirectional"))
    )
    (net (code "47") (name "unconnected-(U2-AUX_CL-Pad7)") (class "Default")
      (node (ref "U2") (pin "7") (pinfunction "AUX_CL_7") (pintype "bidirectional"))
    )
    (net (code "48") (name "unconnected-(U2-AUX_DA-Pad21)") (class "Default")
      (node (ref "U2") (pin "21") (pinfunction "AUX_DA_21") (pintype "bidirectional"))
    )
    (net (code "49") (name "unconnected-(U5-CTS-Pad9)") (class "Default")
      (node (ref "U5") (pin "9") (pinfunction "CTS_9") (pintype "bidirectional"))
    )
    (net (code "50") (name "unconnected-(U5-DCD-Pad12)") (class "Default")
      (node (ref "U5") (pin "12") (pinfunction "DCD_12") (pintype "bidirectional"))
    )
    (net (code "51") (name "unconnected-(U5-DSR-Pad10)") (class "Default")
      (node (ref "U5") (pin "10") (pinfunction "DSR_10") (pintype "bidirectional"))
    )
    (net (code "52") (name "unconnected-(U5-R232-Pad15)") (class "Default")
      (node (ref "U5") (pin "15") (pinfunction "R232_15") (pintype "bidirectional"))
    )
    (net (code "53") (name "unconnected-(U5-RI-Pad11)") (class "Default")
      (node (ref "U5") (pin "11") (pinfunction "RI_11") (pintype "bidirectional"))
    )
    (net (code "54") (name "unconnected-(USB-ID-Pad4)") (class "Default")
      (node (ref "USB") (pin "4") (pinfunction "ID_4") (pintype "passive"))
    )
  )
)
